# E2_Training_555_coincell.net
KiCad netlist of a schematic drawn in EAGLE
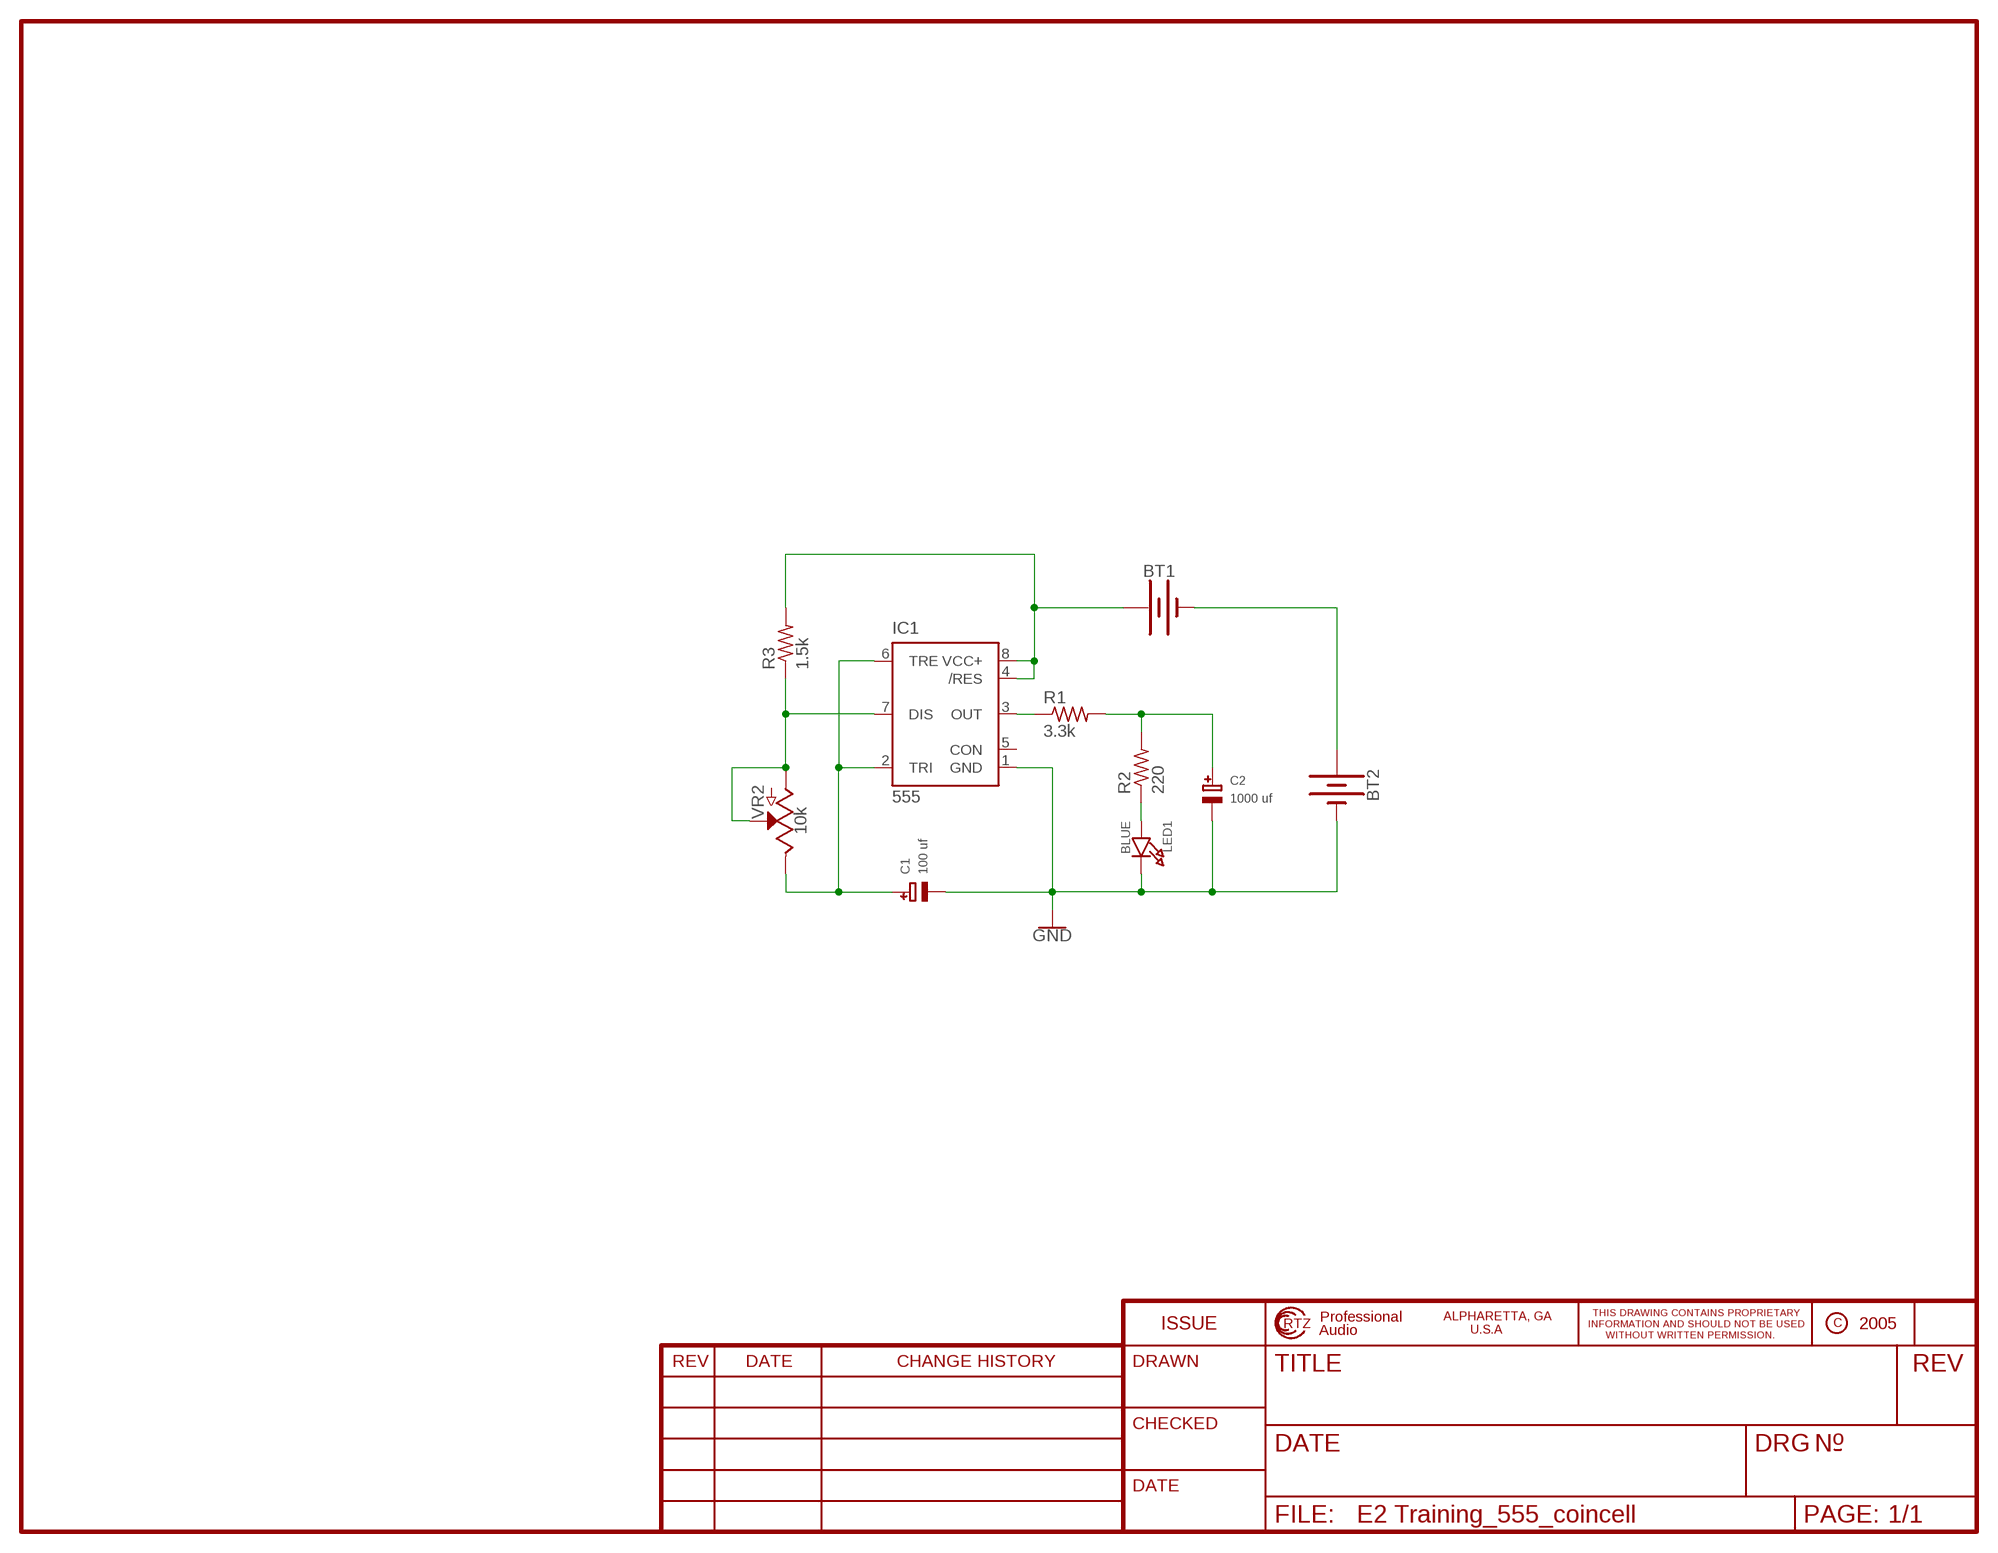
[diagram p0: schematic, sheet 1]

(export (version "E")
  (design (tool "Eeschema 10.0.6"))
  (components
    (comp (ref "BT1")
      (value "BATTERY-20MM_PTH")
      (footprint "eagle-import:BATTCOM_20MM_PTH")
      (libsource (lib "eagle-import") (part "BATTERY-20MM_PTH"))
    )
    (comp (ref "BT2")
      (value "BATTERY-20MM_PTH")
      (footprint "eagle-import:BATTCOM_20MM_PTH")
      (libsource (lib "eagle-import") (part "BATTERY-20MM_PTH"))
    )
    (comp (ref "C1")
      (value "100 uf")
      (footprint "eagle-import:EIA7343-31_D-R")
      (libsource (lib "eagle-import") (part "CAP_TANTALUMD/7343_REFLOW"))
    )
    (comp (ref "C2")
      (value "1000 uf")
      (footprint "eagle-import:EIA7343-31_D-R")
      (libsource (lib "eagle-import") (part "CAP_TANTALUMD/7343_REFLOW"))
    )
    (comp (ref "IC1")
      (value "555")
      (footprint "eagle-import:SO08")
      (libsource (lib "eagle-import") (part "555D"))
    )
    (comp (ref "LED1")
      (value "BLUE")
      (footprint "eagle-import:CHIPLED_0805")
      (libsource (lib "eagle-import") (part "LED0805"))
    )
    (comp (ref "R1")
      (value "3.3k")
      (footprint "eagle-import:M0805")
      (libsource (lib "eagle-import") (part "R-US_M0805"))
    )
    (comp (ref "R2")
      (value "220")
      (footprint "eagle-import:M0805")
      (libsource (lib "eagle-import") (part "R-US_M0805"))
    )
    (comp (ref "R3")
      (value "1.5k")
      (footprint "eagle-import:M0805")
      (libsource (lib "eagle-import") (part "R-US_M0805"))
    )
    (comp (ref "VR2")
      (value "10k")
      (footprint "eagle-import:POT-PTH-ALPS")
      (libsource (lib "eagle-import") (part "POTENTIOMETER-PTH-9MM-1/20W-20%"))
    )
  )
  (nets
    (net (code "1") (name "GND") (class "Default")
      (node (ref "BT2") (pin "2") (pinfunction "-_2") (pintype "power_in"))
      (node (ref "C1") (pin "-") (pinfunction "-_-") (pintype "passive"))
      (node (ref "C2") (pin "-") (pinfunction "-_-") (pintype "passive"))
      (node (ref "IC1") (pin "1") (pinfunction "GND_1") (pintype "power_in"))
      (node (ref "LED1") (pin "C") (pinfunction "C_C") (pintype "passive"))
    )
    (net (code "2") (name "Net-(BT1-+)") (class "Default")
      (node (ref "BT1") (pin "1") (pinfunction "+_1") (pintype "power_in"))
      (node (ref "IC1") (pin "4") (pinfunction "/RES_4") (pintype "input"))
      (node (ref "IC1") (pin "8") (pinfunction "VCC+_8") (pintype "power_in"))
      (node (ref "R3") (pin "2") (pinfunction "2_2") (pintype "passive"))
    )
    (net (code "3") (name "Net-(BT1--)") (class "Default")
      (node (ref "BT1") (pin "2") (pinfunction "-_2") (pintype "power_in"))
      (node (ref "BT2") (pin "1") (pinfunction "+_1") (pintype "power_in"))
    )
    (net (code "4") (name "Net-(C2-Pad+)") (class "Default")
      (node (ref "C2") (pin "+") (pinfunction "+_+") (pintype "passive"))
      (node (ref "R1") (pin "2") (pinfunction "2_2") (pintype "passive"))
      (node (ref "R2") (pin "2") (pinfunction "2_2") (pintype "passive"))
    )
    (net (code "5") (name "Net-(IC1-DIS)") (class "Default")
      (node (ref "IC1") (pin "7") (pinfunction "DIS_7") (pintype "input"))
      (node (ref "R3") (pin "1") (pinfunction "1_1") (pintype "passive"))
      (node (ref "VR2") (pin "P$2") (pinfunction "S_P$2") (pintype "passive"))
      (node (ref "VR2") (pin "P$3") (pinfunction "A_P$3") (pintype "passive"))
    )
    (net (code "6") (name "Net-(IC1-OUT)") (class "Default")
      (node (ref "IC1") (pin "3") (pinfunction "OUT_3") (pintype "output"))
      (node (ref "R1") (pin "1") (pinfunction "1_1") (pintype "passive"))
    )
    (net (code "7") (name "Net-(IC1-TRE)") (class "Default")
      (node (ref "C1") (pin "+") (pinfunction "+_+") (pintype "passive"))
      (node (ref "IC1") (pin "2") (pinfunction "TRI_2") (pintype "input"))
      (node (ref "IC1") (pin "6") (pinfunction "TRE_6") (pintype "input"))
      (node (ref "VR2") (pin "P$1") (pinfunction "E_P$1") (pintype "passive"))
    )
    (net (code "8") (name "Net-(LED1-PadA)") (class "Default")
      (node (ref "LED1") (pin "A") (pinfunction "A_A") (pintype "passive"))
      (node (ref "R2") (pin "1") (pinfunction "1_1") (pintype "passive"))
    )
    (net (code "9") (name "unconnected-(IC1-CON-Pad5)") (class "Default")
      (node (ref "IC1") (pin "5") (pinfunction "CON_5") (pintype "input"))
    )
  )
)
